# Main.net
KiCad netlist of a schematic drawn in Altium Designer
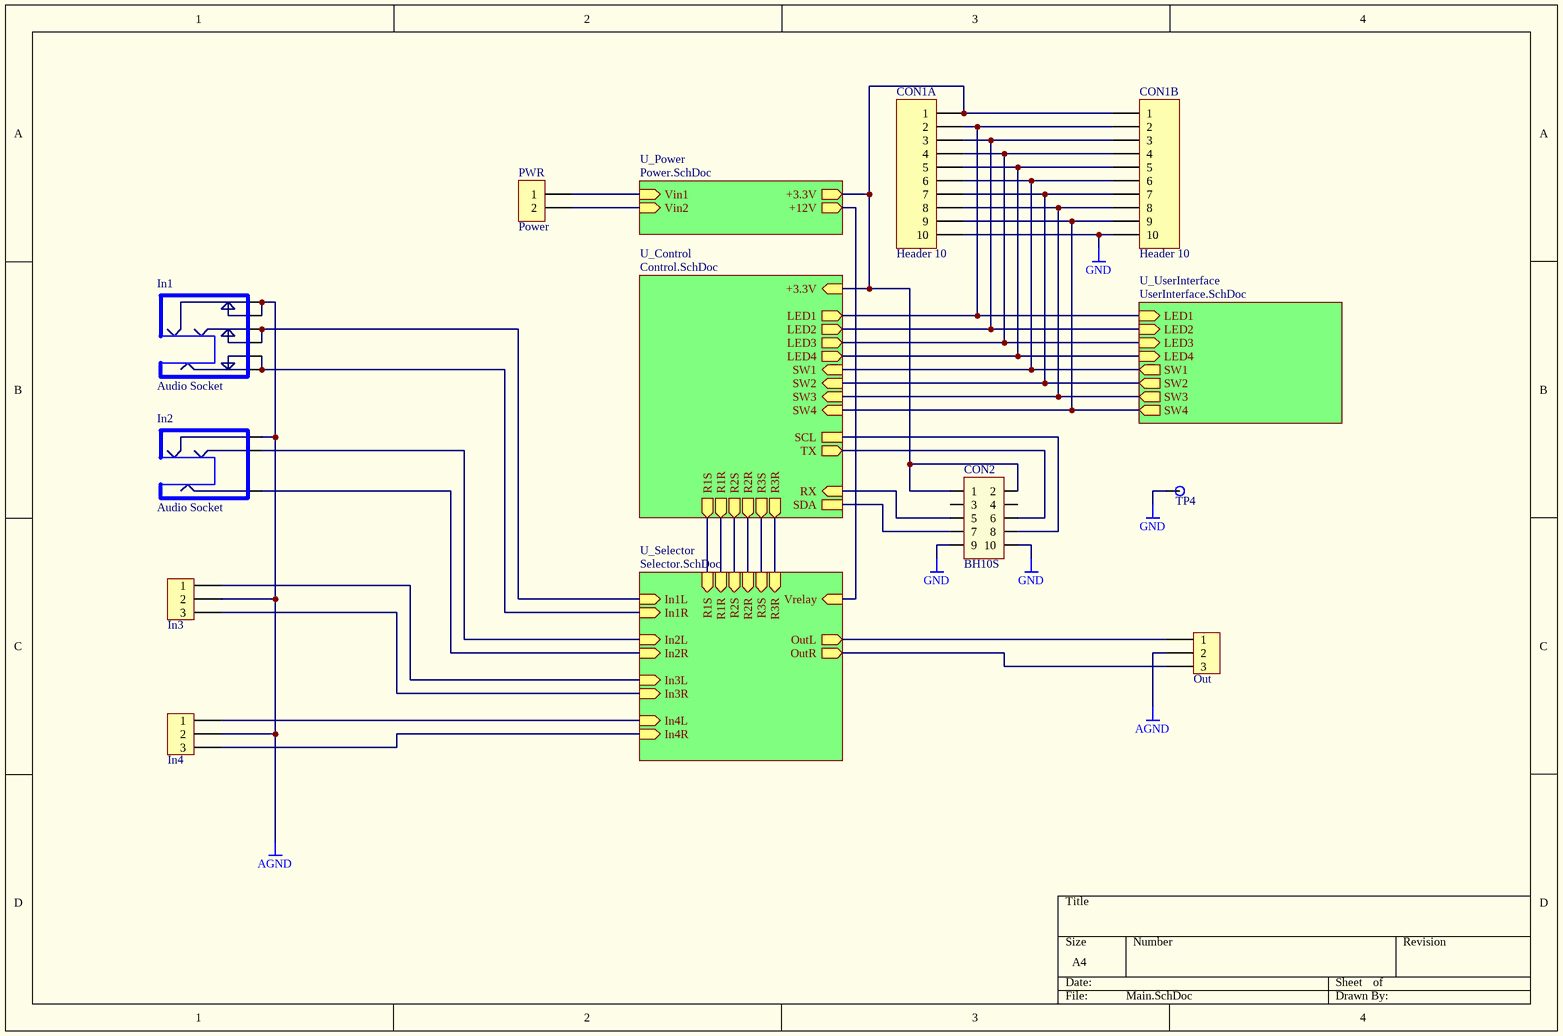
[diagram p0: Main.SchDoc]

(export (version "E")
  (design (tool "Eeschema 10.0.6"))
  (components
    (comp (ref "CON1A")
      (value "Header 10")
      (footprint "JP10")
      (description "Header, 10-Pin")
      (fields (field (name "MANUFACTURER") "Generic Components"))
      (libsource (lib "Miscellaneous Connectors") (part "Header 10"))
    )
    (comp (ref "CON1B")
      (value "Header 10")
      (footprint "JP10")
      (description "Header, 10-Pin")
      (fields (field (name "MANUFACTURER") "Generic Components"))
      (libsource (lib "") (part "Header 10_1"))
    )
    (comp (ref "CON2")
      (value "BH10S")
      (footprint "BH10S")
      (description "BH10S-side mounted")
      (libsource (lib "MainSchlib") (part "CON2x5"))
    )
    (comp (ref "In1")
      (value "Audio Socket")
      (footprint "Schurter4803.2330")
      (libsource (lib "*") (part "SOCKET_AUDIO_3WAY_SW"))
    )
    (comp (ref "In2")
      (value "Audio Socket")
      (footprint "MULTICOMP-MJ4435-R")
      (libsource (lib "*") (part "SOCKET_AUDIO_3WAY_NOSW"))
    )
    (comp (ref "In3")
      (value "CON3")
      (footprint "CON_WS03S")
      (description "Connector")
      (libsource (lib "*") (part "CON3"))
    )
    (comp (ref "In4")
      (value "CON3")
      (footprint "CON_WS03S")
      (description "Connector")
      (libsource (lib "*") (part "CON3"))
    )
    (comp (ref "Out")
      (value "CON3")
      (footprint "CON_WS03S")
      (description "Connector")
      (libsource (lib "") (part "CON3_1"))
    )
    (comp (ref "PWR")
      (value "Power")
      (footprint "CONN_TOP_2P")
      (description "Connector")
      (libsource (lib "*") (part "CON2"))
    )
    (comp (ref "TP4") (value "TESTPAD") (footprint "MISC_PAD-36/65") (libsource (lib "*") (part "TESTPAD")))
  )
  (nets
    (net (code "1") (name "/+3.3V") (class "Default")
      (node (ref "CON1A") (pin "1") (pinfunction "1_1") (pintype "passive"))
      (node (ref "CON1B") (pin "1") (pinfunction "1_1") (pintype "passive"))
      (node (ref "CON2") (pin "1") (pinfunction "1_1") (pintype "passive"))
      (node (ref "CON2") (pin "2") (pinfunction "2_2") (pintype "passive"))
    )
    (net (code "3") (name "/In1L") (class "Default")
      (node (ref "In1") (pin "1") (pinfunction "L_1") (pintype "passive"))
      (node (ref "In1") (pin "6") (pinfunction "L_6") (pintype "passive"))
    )
    (net (code "4") (name "/In1R") (class "Default")
      (node (ref "In1") (pin "2") (pinfunction "R_2") (pintype "passive"))
      (node (ref "In1") (pin "5") (pinfunction "R_5") (pintype "passive"))
    )
    (net (code "5") (name "/In2L") (class "Default")
      (node (ref "In2") (pin "3") (pinfunction "L_3") (pintype "passive"))
    )
    (net (code "6") (name "/In2R") (class "Default")
      (node (ref "In2") (pin "2") (pinfunction "R_2") (pintype "passive"))
    )
    (net (code "7") (name "/In3L") (class "Default")
      (node (ref "In3") (pin "1") (pinfunction "1_1") (pintype "passive"))
    )
    (net (code "8") (name "/In3R") (class "Default")
      (node (ref "In3") (pin "3") (pinfunction "3_3") (pintype "passive"))
    )
    (net (code "9") (name "/In4L") (class "Default")
      (node (ref "In4") (pin "1") (pinfunction "1_1") (pintype "passive"))
    )
    (net (code "10") (name "/In4R") (class "Default")
      (node (ref "In4") (pin "3") (pinfunction "3_3") (pintype "passive"))
    )
    (net (code "11") (name "/LED1") (class "Default")
      (node (ref "CON1A") (pin "2") (pinfunction "2_2") (pintype "passive"))
      (node (ref "CON1B") (pin "2") (pinfunction "2_2") (pintype "passive"))
    )
    (net (code "12") (name "/LED2") (class "Default")
      (node (ref "CON1A") (pin "3") (pinfunction "3_3") (pintype "passive"))
      (node (ref "CON1B") (pin "3") (pinfunction "3_3") (pintype "passive"))
    )
    (net (code "13") (name "/LED3") (class "Default")
      (node (ref "CON1A") (pin "4") (pinfunction "4_4") (pintype "passive"))
      (node (ref "CON1B") (pin "4") (pinfunction "4_4") (pintype "passive"))
    )
    (net (code "14") (name "/LED4") (class "Default")
      (node (ref "CON1A") (pin "5") (pinfunction "5_5") (pintype "passive"))
      (node (ref "CON1B") (pin "5") (pinfunction "5_5") (pintype "passive"))
    )
    (net (code "15") (name "/OutL") (class "Default")
      (node (ref "Out") (pin "1") (pinfunction "1_1") (pintype "passive"))
    )
    (net (code "16") (name "/OutR") (class "Default")
      (node (ref "Out") (pin "3") (pinfunction "3_3") (pintype "passive"))
    )
    (net (code "23") (name "/RX") (class "Default")
      (node (ref "CON2") (pin "5") (pinfunction "5_5") (pintype "passive"))
    )
    (net (code "24") (name "/SCL") (class "Default")
      (node (ref "CON2") (pin "8") (pinfunction "8_8") (pintype "passive"))
    )
    (net (code "25") (name "/SDA") (class "Default")
      (node (ref "CON2") (pin "7") (pinfunction "7_7") (pintype "passive"))
    )
    (net (code "26") (name "/SW1") (class "Default")
      (node (ref "CON1A") (pin "6") (pinfunction "6_6") (pintype "passive"))
      (node (ref "CON1B") (pin "6") (pinfunction "6_6") (pintype "passive"))
    )
    (net (code "27") (name "/SW2") (class "Default")
      (node (ref "CON1A") (pin "7") (pinfunction "7_7") (pintype "passive"))
      (node (ref "CON1B") (pin "7") (pinfunction "7_7") (pintype "passive"))
    )
    (net (code "28") (name "/SW3") (class "Default")
      (node (ref "CON1A") (pin "8") (pinfunction "8_8") (pintype "passive"))
      (node (ref "CON1B") (pin "8") (pinfunction "8_8") (pintype "passive"))
    )
    (net (code "29") (name "/SW4") (class "Default")
      (node (ref "CON1A") (pin "9") (pinfunction "9_9") (pintype "passive"))
      (node (ref "CON1B") (pin "9") (pinfunction "9_9") (pintype "passive"))
    )
    (net (code "30") (name "/TX") (class "Default")
      (node (ref "CON2") (pin "6") (pinfunction "6_6") (pintype "passive"))
    )
    (net (code "31") (name "/Vin1") (class "Default")
      (node (ref "PWR") (pin "1") (pinfunction "1_1") (pintype "passive"))
    )
    (net (code "32") (name "/Vin2") (class "Default")
      (node (ref "PWR") (pin "2") (pinfunction "2_2") (pintype "passive"))
    )
    (net (code "33") (name "AGND") (class "Default")
      (node (ref "In1") (pin "3") (pinfunction "GND_3") (pintype "passive"))
      (node (ref "In1") (pin "4") (pinfunction "GND_4") (pintype "passive"))
      (node (ref "In2") (pin "1") (pinfunction "GND_1") (pintype "passive"))
      (node (ref "In3") (pin "2") (pinfunction "2_2") (pintype "passive"))
      (node (ref "In4") (pin "2") (pinfunction "2_2") (pintype "passive"))
      (node (ref "Out") (pin "2") (pinfunction "2_2") (pintype "passive"))
    )
    (net (code "34") (name "GND") (class "Default")
      (node (ref "CON1A") (pin "10") (pinfunction "10_10") (pintype "passive"))
      (node (ref "CON1B") (pin "10") (pinfunction "10_10") (pintype "passive"))
      (node (ref "CON2") (pin "10") (pinfunction "10_10") (pintype "passive"))
      (node (ref "CON2") (pin "9") (pinfunction "9_9") (pintype "passive"))
      (node (ref "TP4") (pin "1") (pinfunction "1_1") (pintype "passive"))
    )
    (net (code "35") (name "unconnected-(CON2-Pad3)") (class "Default")
      (node (ref "CON2") (pin "3") (pinfunction "3_3") (pintype "passive"))
    )
    (net (code "36") (name "unconnected-(CON2-Pad4)") (class "Default")
      (node (ref "CON2") (pin "4") (pinfunction "4_4") (pintype "passive"))
    )
  )
)
